# bitslice.net
KiCad netlist of a schematic drawn in EAGLE
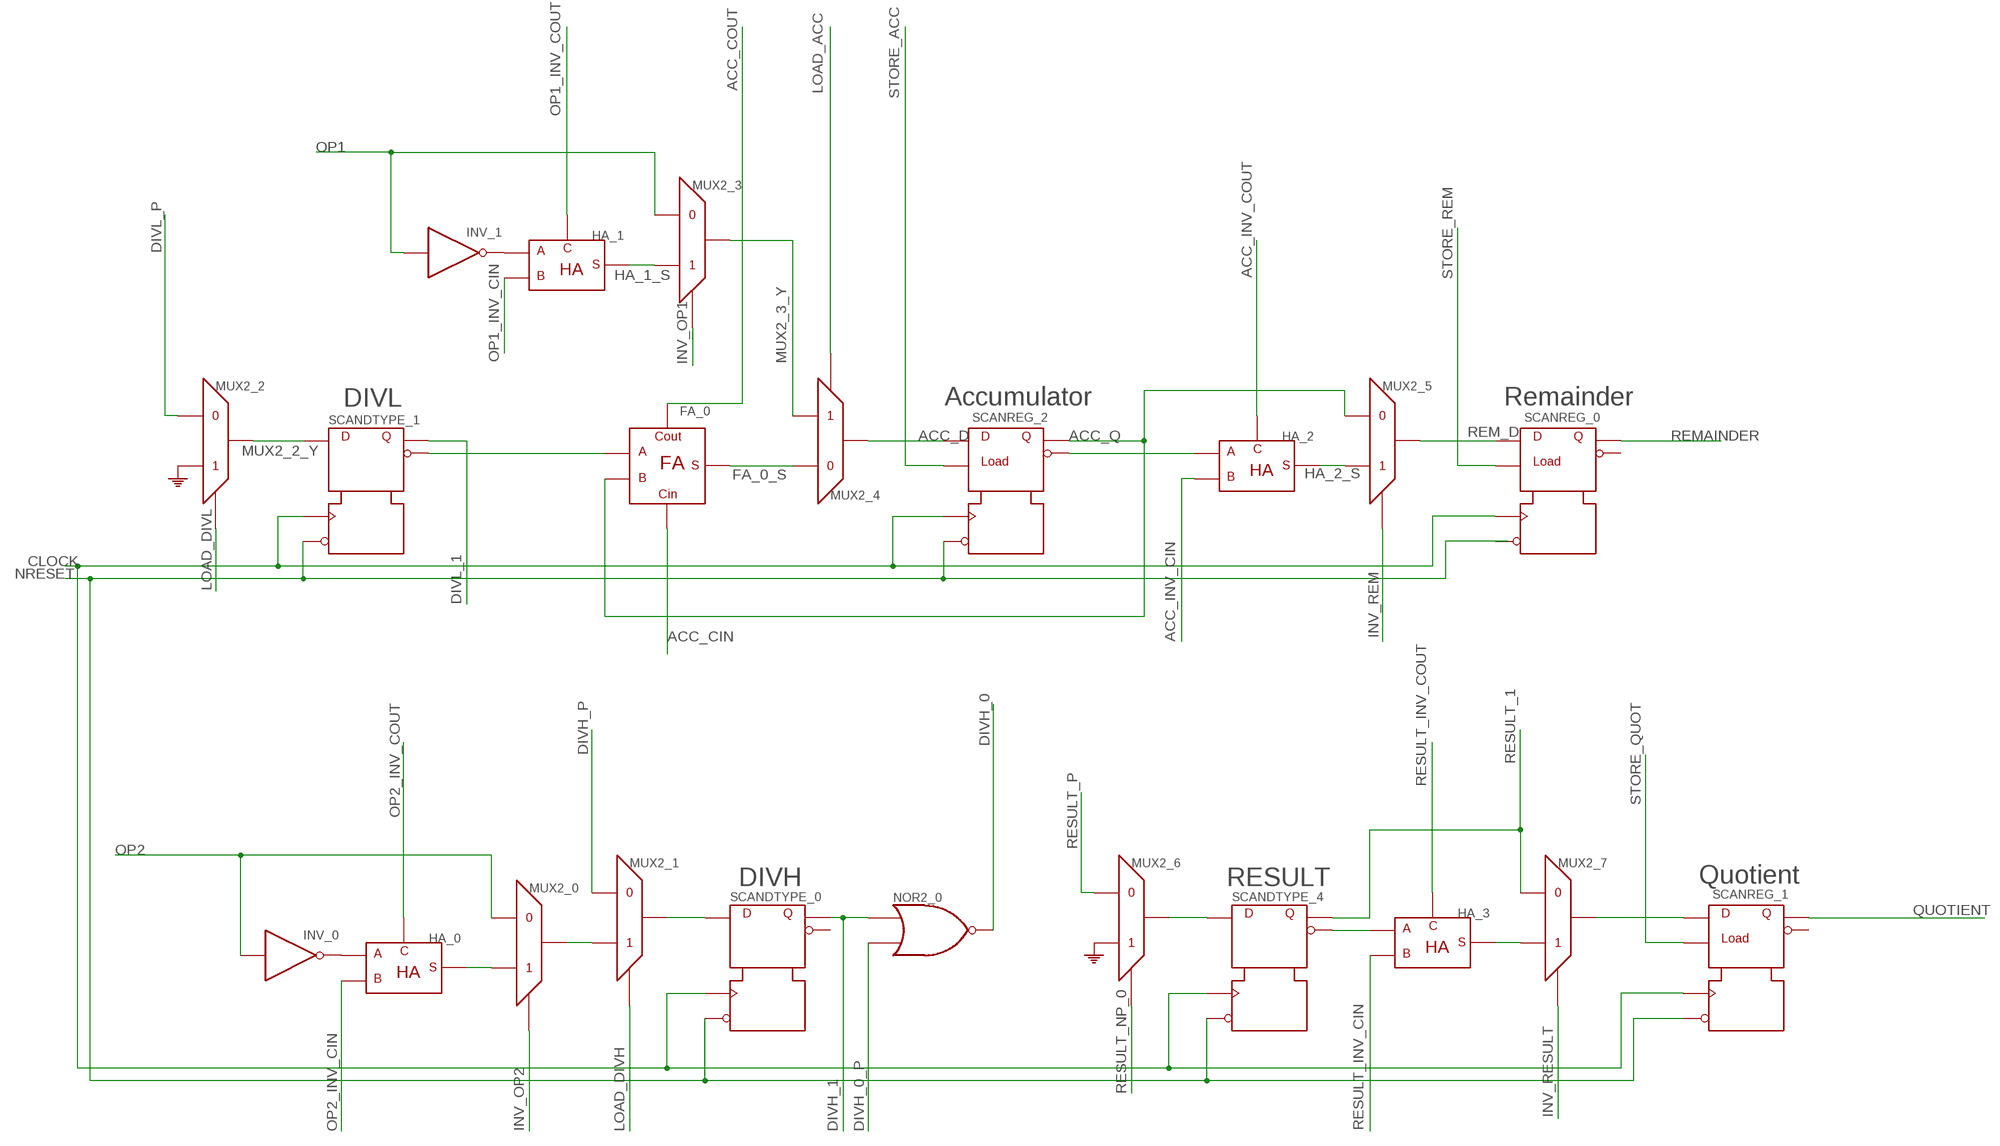
[diagram p0: schematic, sheet 1]

(export (version "E")
  (design (tool "Eeschema 10.0.6"))
  (components
    (comp (ref "FA_0")
      (value "FULLADDER")
      (footprint "eagle-import:5PIN")
      (libsource (lib "eagle-import") (part "FULLADDER"))
    )
    (comp (ref "HA_0")
      (value "HALFADDER")
      (footprint "eagle-import:5PIN")
      (libsource (lib "eagle-import") (part "HALFADDER"))
    )
    (comp (ref "HA_1")
      (value "HALFADDER")
      (footprint "eagle-import:5PIN")
      (libsource (lib "eagle-import") (part "HALFADDER"))
    )
    (comp (ref "HA_2")
      (value "HALFADDER")
      (footprint "eagle-import:5PIN")
      (libsource (lib "eagle-import") (part "HALFADDER"))
    )
    (comp (ref "HA_3")
      (value "HALFADDER")
      (footprint "eagle-import:5PIN")
      (libsource (lib "eagle-import") (part "HALFADDER"))
    )
    (comp (ref "INV_0")
      (value "INV")
      (footprint "eagle-import:3PIN")
      (libsource (lib "eagle-import") (part "INV"))
    )
    (comp (ref "INV_1")
      (value "INV")
      (footprint "eagle-import:3PIN")
      (libsource (lib "eagle-import") (part "INV"))
    )
    (comp (ref "MUX2_0")
      (value "MUX2")
      (footprint "eagle-import:5PIN")
      (libsource (lib "eagle-import") (part "MUX2"))
    )
    (comp (ref "MUX2_1")
      (value "MUX2")
      (footprint "eagle-import:5PIN")
      (libsource (lib "eagle-import") (part "MUX2"))
    )
    (comp (ref "MUX2_2")
      (value "MUX2")
      (footprint "eagle-import:5PIN")
      (libsource (lib "eagle-import") (part "MUX2"))
    )
    (comp (ref "MUX2_3")
      (value "MUX2")
      (footprint "eagle-import:5PIN")
      (libsource (lib "eagle-import") (part "MUX2"))
    )
    (comp (ref "MUX2_4")
      (value "MUX2")
      (footprint "eagle-import:5PIN")
      (libsource (lib "eagle-import") (part "MUX2"))
    )
    (comp (ref "MUX2_5")
      (value "MUX2")
      (footprint "eagle-import:5PIN")
      (libsource (lib "eagle-import") (part "MUX2"))
    )
    (comp (ref "MUX2_6")
      (value "MUX2")
      (footprint "eagle-import:5PIN")
      (libsource (lib "eagle-import") (part "MUX2"))
    )
    (comp (ref "MUX2_7")
      (value "MUX2")
      (footprint "eagle-import:5PIN")
      (libsource (lib "eagle-import") (part "MUX2"))
    )
    (comp (ref "NOR2_0")
      (value "NOR2")
      (footprint "eagle-import:3PIN")
      (libsource (lib "eagle-import") (part "NOR2"))
    )
    (comp (ref "SCANDTYPE_0")
      (value "SCANDTYPE")
      (footprint "eagle-import:5PIN")
      (libsource (lib "eagle-import") (part "SCANDTYPE"))
    )
    (comp (ref "SCANDTYPE_1")
      (value "SCANDTYPE")
      (footprint "eagle-import:5PIN")
      (libsource (lib "eagle-import") (part "SCANDTYPE"))
    )
    (comp (ref "SCANDTYPE_4")
      (value "SCANDTYPE")
      (footprint "eagle-import:5PIN")
      (libsource (lib "eagle-import") (part "SCANDTYPE"))
    )
    (comp (ref "SCANREG_0")
      (value "SCANREG")
      (footprint "eagle-import:6PIN")
      (libsource (lib "eagle-import") (part "SCANREG"))
    )
    (comp (ref "SCANREG_1")
      (value "SCANREG")
      (footprint "eagle-import:6PIN")
      (libsource (lib "eagle-import") (part "SCANREG"))
    )
    (comp (ref "SCANREG_2")
      (value "SCANREG")
      (footprint "eagle-import:6PIN")
      (libsource (lib "eagle-import") (part "SCANREG"))
    )
  )
  (nets
    (net (code "1") (name "/ACC_CIN") (class "Default")
      (node (ref "FA_0") (pin "P$3") (pinfunction "CIN_P$3") (pintype "bidirectional"))
    )
    (net (code "2") (name "/ACC_COUT") (class "Default")
      (node (ref "FA_0") (pin "P$4") (pinfunction "COUT_P$4") (pintype "bidirectional"))
    )
    (net (code "3") (name "/ACC_D") (class "Default")
      (node (ref "MUX2_4") (pin "P$3") (pinfunction "P$3_P$3") (pintype "bidirectional"))
      (node (ref "SCANREG_2") (pin "P$2") (pinfunction "D_P$2") (pintype "bidirectional"))
    )
    (net (code "4") (name "/ACC_INV_CIN") (class "Default")
      (node (ref "HA_2") (pin "P$2") (pinfunction "B_P$2") (pintype "bidirectional"))
    )
    (net (code "5") (name "/ACC_INV_COUT") (class "Default")
      (node (ref "HA_2") (pin "P$3") (pinfunction "COUT_P$3") (pintype "bidirectional"))
    )
    (net (code "6") (name "/ACC_Q") (class "Default")
      (node (ref "FA_0") (pin "P$2") (pinfunction "B_P$2") (pintype "bidirectional"))
      (node (ref "MUX2_5") (pin "P$1") (pinfunction "P$1_P$1") (pintype "bidirectional"))
      (node (ref "SCANREG_2") (pin "P$6") (pinfunction "Q_P$6") (pintype "bidirectional"))
    )
    (net (code "7") (name "/CLOCK") (class "Default")
      (node (ref "SCANDTYPE_0") (pin "P$1") (pinfunction "CLOCK_P$1") (pintype "bidirectional"))
      (node (ref "SCANDTYPE_1") (pin "P$1") (pinfunction "CLOCK_P$1") (pintype "bidirectional"))
      (node (ref "SCANDTYPE_4") (pin "P$1") (pinfunction "CLOCK_P$1") (pintype "bidirectional"))
      (node (ref "SCANREG_0") (pin "P$1") (pinfunction "CLOCK_P$1") (pintype "bidirectional"))
      (node (ref "SCANREG_1") (pin "P$1") (pinfunction "CLOCK_P$1") (pintype "bidirectional"))
      (node (ref "SCANREG_2") (pin "P$1") (pinfunction "CLOCK_P$1") (pintype "bidirectional"))
    )
    (net (code "8") (name "/DIVH_0") (class "Default")
      (node (ref "NOR2_0") (pin "P$3") (pinfunction "O_P$3") (pintype "output"))
    )
    (net (code "9") (name "/DIVH_0_P") (class "Default")
      (node (ref "NOR2_0") (pin "P$2") (pinfunction "I1_P$2") (pintype "input"))
    )
    (net (code "10") (name "/DIVH_1") (class "Default")
      (node (ref "NOR2_0") (pin "P$1") (pinfunction "I0_P$1") (pintype "input"))
      (node (ref "SCANDTYPE_0") (pin "P$5") (pinfunction "Q_P$5") (pintype "bidirectional"))
    )
    (net (code "11") (name "/DIVH_P") (class "Default")
      (node (ref "MUX2_1") (pin "P$1") (pinfunction "P$1_P$1") (pintype "bidirectional"))
    )
    (net (code "12") (name "/DIVL_1") (class "Default")
      (node (ref "SCANDTYPE_1") (pin "P$5") (pinfunction "Q_P$5") (pintype "bidirectional"))
    )
    (net (code "13") (name "/DIVL_P") (class "Default")
      (node (ref "MUX2_2") (pin "P$1") (pinfunction "P$1_P$1") (pintype "bidirectional"))
    )
    (net (code "14") (name "/FA_0_S") (class "Default")
      (node (ref "FA_0") (pin "P$5") (pinfunction "S_P$5") (pintype "bidirectional"))
      (node (ref "MUX2_4") (pin "P$1") (pinfunction "P$1_P$1") (pintype "bidirectional"))
    )
    (net (code "15") (name "/HA_1_S") (class "Default")
      (node (ref "HA_1") (pin "P$4") (pinfunction "S_P$4") (pintype "bidirectional"))
      (node (ref "MUX2_3") (pin "P$2") (pinfunction "P$2_P$2") (pintype "bidirectional"))
    )
    (net (code "16") (name "/HA_2_S") (class "Default")
      (node (ref "HA_2") (pin "P$4") (pinfunction "S_P$4") (pintype "bidirectional"))
      (node (ref "MUX2_5") (pin "P$2") (pinfunction "P$2_P$2") (pintype "bidirectional"))
    )
    (net (code "17") (name "/INV_OP1") (class "Default")
      (node (ref "MUX2_3") (pin "P$4") (pinfunction "P$4_P$4") (pintype "bidirectional"))
    )
    (net (code "18") (name "/INV_OP2") (class "Default")
      (node (ref "MUX2_0") (pin "P$4") (pinfunction "P$4_P$4") (pintype "bidirectional"))
    )
    (net (code "19") (name "/INV_REM") (class "Default")
      (node (ref "MUX2_5") (pin "P$4") (pinfunction "P$4_P$4") (pintype "bidirectional"))
    )
    (net (code "20") (name "/INV_RESULT") (class "Default")
      (node (ref "MUX2_7") (pin "P$4") (pinfunction "P$4_P$4") (pintype "bidirectional"))
    )
    (net (code "21") (name "/LOAD_ACC") (class "Default")
      (node (ref "MUX2_4") (pin "P$4") (pinfunction "P$4_P$4") (pintype "bidirectional"))
    )
    (net (code "22") (name "/LOAD_DIVH") (class "Default")
      (node (ref "MUX2_1") (pin "P$4") (pinfunction "P$4_P$4") (pintype "bidirectional"))
    )
    (net (code "23") (name "/LOAD_DIVL") (class "Default")
      (node (ref "MUX2_2") (pin "P$4") (pinfunction "P$4_P$4") (pintype "bidirectional"))
    )
    (net (code "24") (name "/MUX2_2_Y") (class "Default")
      (node (ref "MUX2_2") (pin "P$3") (pinfunction "P$3_P$3") (pintype "bidirectional"))
      (node (ref "SCANDTYPE_1") (pin "P$2") (pinfunction "D_P$2") (pintype "bidirectional"))
    )
    (net (code "25") (name "/MUX2_3_Y") (class "Default")
      (node (ref "MUX2_3") (pin "P$3") (pinfunction "P$3_P$3") (pintype "bidirectional"))
      (node (ref "MUX2_4") (pin "P$2") (pinfunction "P$2_P$2") (pintype "bidirectional"))
    )
    (net (code "26") (name "/NRESET") (class "Default")
      (node (ref "SCANDTYPE_0") (pin "P$4") (pinfunction "NRESET_P$4") (pintype "bidirectional"))
      (node (ref "SCANDTYPE_1") (pin "P$4") (pinfunction "NRESET_P$4") (pintype "bidirectional"))
      (node (ref "SCANDTYPE_4") (pin "P$4") (pinfunction "NRESET_P$4") (pintype "bidirectional"))
      (node (ref "SCANREG_1") (pin "P$5") (pinfunction "NRESET_P$5") (pintype "bidirectional"))
      (node (ref "SCANREG_2") (pin "P$5") (pinfunction "NRESET_P$5") (pintype "bidirectional"))
    )
    (net (code "27") (name "/OP1") (class "Default")
      (node (ref "INV_1") (pin "P$1") (pinfunction "I_P$1") (pintype "input"))
      (node (ref "MUX2_3") (pin "P$1") (pinfunction "P$1_P$1") (pintype "bidirectional"))
    )
    (net (code "28") (name "/OP1_INV_CIN") (class "Default")
      (node (ref "HA_1") (pin "P$2") (pinfunction "B_P$2") (pintype "bidirectional"))
    )
    (net (code "29") (name "/OP1_INV_COUT") (class "Default")
      (node (ref "HA_1") (pin "P$3") (pinfunction "COUT_P$3") (pintype "bidirectional"))
    )
    (net (code "30") (name "/OP2") (class "Default")
      (node (ref "INV_0") (pin "P$1") (pinfunction "I_P$1") (pintype "input"))
      (node (ref "MUX2_0") (pin "P$1") (pinfunction "P$1_P$1") (pintype "bidirectional"))
    )
    (net (code "31") (name "/OP2_INV_CIN") (class "Default")
      (node (ref "HA_0") (pin "P$2") (pinfunction "B_P$2") (pintype "bidirectional"))
    )
    (net (code "32") (name "/OP2_INV_COUT") (class "Default")
      (node (ref "HA_0") (pin "P$3") (pinfunction "COUT_P$3") (pintype "bidirectional"))
    )
    (net (code "33") (name "/QUOTIENT") (class "Default")
      (node (ref "SCANREG_1") (pin "P$6") (pinfunction "Q_P$6") (pintype "bidirectional"))
    )
    (net (code "34") (name "/REMAINDER") (class "Default")
      (node (ref "SCANREG_0") (pin "P$6") (pinfunction "Q_P$6") (pintype "bidirectional"))
    )
    (net (code "35") (name "/REM_D") (class "Default")
      (node (ref "MUX2_5") (pin "P$3") (pinfunction "P$3_P$3") (pintype "bidirectional"))
      (node (ref "SCANREG_0") (pin "P$2") (pinfunction "D_P$2") (pintype "bidirectional"))
    )
    (net (code "36") (name "/RESULT_1") (class "Default")
      (node (ref "MUX2_7") (pin "P$1") (pinfunction "P$1_P$1") (pintype "bidirectional"))
      (node (ref "SCANDTYPE_4") (pin "P$5") (pinfunction "Q_P$5") (pintype "bidirectional"))
    )
    (net (code "37") (name "/RESULT_INV_CIN") (class "Default")
      (node (ref "HA_3") (pin "P$2") (pinfunction "B_P$2") (pintype "bidirectional"))
    )
    (net (code "38") (name "/RESULT_INV_COUT") (class "Default")
      (node (ref "HA_3") (pin "P$3") (pinfunction "COUT_P$3") (pintype "bidirectional"))
    )
    (net (code "39") (name "/RESULT_NP_0") (class "Default")
      (node (ref "MUX2_6") (pin "P$4") (pinfunction "P$4_P$4") (pintype "bidirectional"))
    )
    (net (code "40") (name "/RESULT_P") (class "Default")
      (node (ref "MUX2_6") (pin "P$1") (pinfunction "P$1_P$1") (pintype "bidirectional"))
    )
    (net (code "41") (name "/STORE_ACC") (class "Default")
      (node (ref "SCANREG_2") (pin "P$3") (pinfunction "LOAD_P$3") (pintype "bidirectional"))
    )
    (net (code "42") (name "/STORE_QUOT") (class "Default")
      (node (ref "SCANREG_1") (pin "P$3") (pinfunction "LOAD_P$3") (pintype "bidirectional"))
    )
    (net (code "43") (name "/STORE_REM") (class "Default")
      (node (ref "SCANREG_0") (pin "P$3") (pinfunction "LOAD_P$3") (pintype "bidirectional"))
    )
    (net (code "44") (name "Net-(FA_0-A)") (class "Default")
      (node (ref "FA_0") (pin "P$1") (pinfunction "A_P$1") (pintype "bidirectional"))
      (node (ref "SCANDTYPE_1") (pin "P$3") (pinfunction "NQ_P$3") (pintype "bidirectional"))
    )
    (net (code "45") (name "Net-(HA_0-A)") (class "Default")
      (node (ref "HA_0") (pin "P$1") (pinfunction "A_P$1") (pintype "bidirectional"))
      (node (ref "INV_0") (pin "P$2") (pinfunction "O_P$2") (pintype "open_collector"))
    )
    (net (code "46") (name "Net-(HA_0-S)") (class "Default")
      (node (ref "HA_0") (pin "P$4") (pinfunction "S_P$4") (pintype "bidirectional"))
      (node (ref "MUX2_0") (pin "P$2") (pinfunction "P$2_P$2") (pintype "bidirectional"))
    )
    (net (code "47") (name "Net-(HA_1-A)") (class "Default")
      (node (ref "HA_1") (pin "P$1") (pinfunction "A_P$1") (pintype "bidirectional"))
      (node (ref "INV_1") (pin "P$2") (pinfunction "O_P$2") (pintype "open_collector"))
    )
    (net (code "48") (name "Net-(HA_2-A)") (class "Default")
      (node (ref "HA_2") (pin "P$1") (pinfunction "A_P$1") (pintype "bidirectional"))
      (node (ref "SCANREG_2") (pin "P$4") (pinfunction "NQ_P$4") (pintype "bidirectional"))
    )
    (net (code "49") (name "Net-(HA_3-A)") (class "Default")
      (node (ref "HA_3") (pin "P$1") (pinfunction "A_P$1") (pintype "bidirectional"))
      (node (ref "SCANDTYPE_4") (pin "P$3") (pinfunction "NQ_P$3") (pintype "bidirectional"))
    )
    (net (code "50") (name "Net-(HA_3-S)") (class "Default")
      (node (ref "HA_3") (pin "P$4") (pinfunction "S_P$4") (pintype "bidirectional"))
      (node (ref "MUX2_7") (pin "P$2") (pinfunction "P$2_P$2") (pintype "bidirectional"))
    )
    (net (code "51") (name "Net-(MUX2_0-PadP$3)") (class "Default")
      (node (ref "MUX2_0") (pin "P$3") (pinfunction "P$3_P$3") (pintype "bidirectional"))
      (node (ref "MUX2_1") (pin "P$2") (pinfunction "P$2_P$2") (pintype "bidirectional"))
    )
    (net (code "52") (name "Net-(SCANDTYPE_0-D)") (class "Default")
      (node (ref "MUX2_1") (pin "P$3") (pinfunction "P$3_P$3") (pintype "bidirectional"))
      (node (ref "SCANDTYPE_0") (pin "P$2") (pinfunction "D_P$2") (pintype "bidirectional"))
    )
    (net (code "53") (name "Net-(SCANDTYPE_4-D)") (class "Default")
      (node (ref "MUX2_6") (pin "P$3") (pinfunction "P$3_P$3") (pintype "bidirectional"))
      (node (ref "SCANDTYPE_4") (pin "P$2") (pinfunction "D_P$2") (pintype "bidirectional"))
    )
    (net (code "54") (name "Net-(SCANREG_1-D)") (class "Default")
      (node (ref "MUX2_7") (pin "P$3") (pinfunction "P$3_P$3") (pintype "bidirectional"))
      (node (ref "SCANREG_1") (pin "P$2") (pinfunction "D_P$2") (pintype "bidirectional"))
    )
    (net (code "55") (name "TIELOW") (class "Default")
      (node (ref "MUX2_2") (pin "P$2") (pinfunction "P$2_P$2") (pintype "bidirectional"))
      (node (ref "MUX2_6") (pin "P$2") (pinfunction "P$2_P$2") (pintype "bidirectional"))
    )
    (net (code "56") (name "unconnected-(SCANDTYPE_0-NQ-PadP$3)") (class "Default")
      (node (ref "SCANDTYPE_0") (pin "P$3") (pinfunction "NQ_P$3") (pintype "bidirectional"))
    )
    (net (code "57") (name "unconnected-(SCANREG_0-NQ-PadP$4)") (class "Default")
      (node (ref "SCANREG_0") (pin "P$4") (pinfunction "NQ_P$4") (pintype "bidirectional"))
    )
    (net (code "58") (name "unconnected-(SCANREG_0-NRESET-PadP$5)") (class "Default")
      (node (ref "SCANREG_0") (pin "P$5") (pinfunction "NRESET_P$5") (pintype "bidirectional"))
    )
    (net (code "59") (name "unconnected-(SCANREG_1-NQ-PadP$4)") (class "Default")
      (node (ref "SCANREG_1") (pin "P$4") (pinfunction "NQ_P$4") (pintype "bidirectional"))
    )
  )
)
